# DRV8301_project.net
KiCad netlist of a schematic drawn in Altium Designer
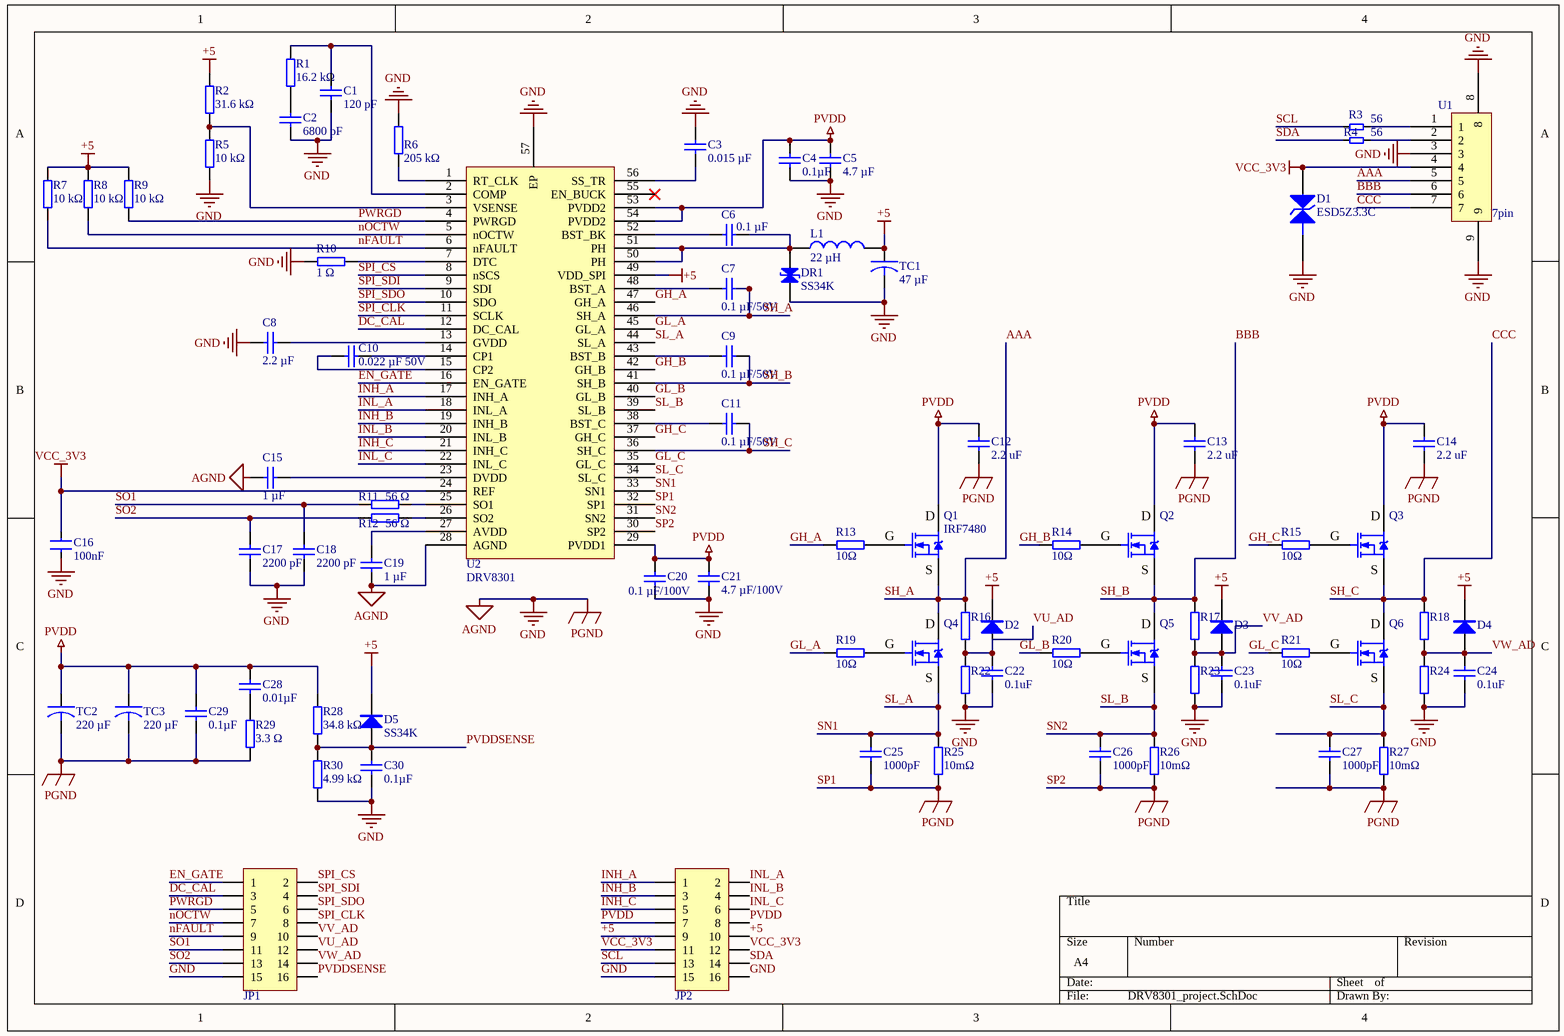
[diagram p0: DRV8301_project.SchDoc]

(export (version "E")
  (design (tool "Eeschema 10.0.6"))
  (components
    (comp (ref "C1") (value "120 pF") (footprint "C 0603_L") (libsource (lib "DRV8301") (part "CAP")))
    (comp (ref "C2") (value "6800 pF") (footprint "C 0603_L") (libsource (lib "DRV8301") (part "CAP")))
    (comp (ref "C3") (value "0.015 µF") (footprint "C 0603_L") (libsource (lib "DRV8301") (part "CAP")))
    (comp (ref "C4") (value "0.1µF") (footprint "C 0603_L") (libsource (lib "DRV8301") (part "CAP")))
    (comp (ref "C5") (value "4.7 µF") (footprint "C 0603_L") (libsource (lib "DRV8301") (part "CAP")))
    (comp (ref "C6") (value "0.1 µF") (footprint "C 0603_L") (libsource (lib "DRV8301") (part "CAP")))
    (comp (ref "C7") (value "0.1 µF/50V") (footprint "C 0603_L") (libsource (lib "DRV8301") (part "CAP")))
    (comp (ref "C8")
      (value "2.2 µF")
      (footprint "C 0603_L")
      (description "2.2 µF  陶瓷电容。大于16V")
      (libsource (lib "DRV8301") (part "CAP"))
    )
    (comp (ref "C9") (value "0.1 µF/50V") (footprint "C 0603_L") (libsource (lib "DRV8301") (part "CAP")))
    (comp (ref "C10")
      (value "0.022 µF 50V")
      (footprint "C 0603_L")
      (description "耐压值要高的陶瓷电容，等于V PIDD1")
      (libsource (lib "DRV8301") (part "CAP"))
    )
    (comp (ref "C11") (value "0.1 µF/50V") (footprint "C 0603_L") (libsource (lib "DRV8301") (part "CAP")))
    (comp (ref "C12") (value "2.2 uF") (footprint "C 0603_L") (libsource (lib "DRV8301") (part "CAP")))
    (comp (ref "C13") (value "2.2 uF") (footprint "C 0603_L") (libsource (lib "DRV8301") (part "CAP")))
    (comp (ref "C14") (value "2.2 uF") (footprint "C 0603_L") (libsource (lib "DRV8301") (part "CAP")))
    (comp (ref "C15") (value "1 µF") (footprint "C 0603_L") (libsource (lib "DRV8301") (part "CAP")))
    (comp (ref "C16")
      (value "100nF")
      (footprint "C 0603_L")
      (description "电容")
      (libsource (lib "DRV8313PWPR") (part "C0603"))
    )
    (comp (ref "C17") (value "2200 pF") (footprint "C 0603_L") (libsource (lib "DRV8301") (part "CAP")))
    (comp (ref "C18") (value "2200 pF") (footprint "C 0603_L") (libsource (lib "DRV8301") (part "CAP")))
    (comp (ref "C19") (value "1 µF") (footprint "C 0603_L") (libsource (lib "DRV8301") (part "CAP")))
    (comp (ref "C20") (value "0.1 µF/100V") (footprint "C 0603_L") (libsource (lib "DRV8301") (part "CAP")))
    (comp (ref "C21") (value "4.7 µF/100V") (footprint "C 0603_L") (libsource (lib "DRV8301") (part "CAP")))
    (comp (ref "C22") (value "0.1uF") (footprint "C 0603_L") (libsource (lib "DRV8301") (part "CAP")))
    (comp (ref "C23") (value "0.1uF") (footprint "C 0603_L") (libsource (lib "DRV8301") (part "CAP")))
    (comp (ref "C24") (value "0.1uF") (footprint "C 0603_L") (libsource (lib "DRV8301") (part "CAP")))
    (comp (ref "C25") (value "1000pF") (footprint "C 0603_L") (libsource (lib "DRV8301") (part "CAP")))
    (comp (ref "C26") (value "1000pF") (footprint "C 0603_L") (libsource (lib "DRV8301") (part "CAP")))
    (comp (ref "C27") (value "1000pF") (footprint "C 0603_L") (libsource (lib "DRV8301") (part "CAP")))
    (comp (ref "C28") (value "0.01µF") (footprint "C 0603_L") (libsource (lib "DRV8301") (part "CAP")))
    (comp (ref "C29") (value "0.1µF") (footprint "C 0603_L") (libsource (lib "DRV8301") (part "CAP")))
    (comp (ref "C30") (value "0.1µF") (footprint "C 0603_L") (libsource (lib "DRV8301") (part "CAP")))
    (comp (ref "D1")
      (value "ESD5Z3.3C")
      (footprint "R 0603_L")
      (description "ESD管")
      (libsource (lib "DRV8313PWPR") (part "ESD"))
    )
    (comp (ref "D2")
      (value "SS34K")
      (footprint "SMA")
      (description "肖特基二极管")
      (fields (field (name "版权归属") "源创客"))
      (libsource (lib "DRV8301") (part "SS34"))
    )
    (comp (ref "D3")
      (value "SS34K")
      (footprint "SMA")
      (description "肖特基二极管")
      (fields (field (name "版权归属") "源创客"))
      (libsource (lib "DRV8301") (part "SS34"))
    )
    (comp (ref "D4")
      (value "SS34K")
      (footprint "SMA")
      (description "肖特基二极管")
      (fields (field (name "版权归属") "源创客"))
      (libsource (lib "DRV8301") (part "SS34"))
    )
    (comp (ref "D5")
      (value "SS34K")
      (footprint "SMA")
      (description "肖特基二极管")
      (fields (field (name "版权归属") "源创客"))
      (libsource (lib "DRV8301") (part "SS34"))
    )
    (comp (ref "DR1")
      (value "SS34K")
      (footprint "SMA")
      (description "瞬态电压抑制二极管")
      (fields (field (name "版权归属") "源创客"))
      (libsource (lib "DRV8301") (part "DR"))
    )
    (comp (ref "JP1")
      (value "Header 8X2")
      (footprint "HDR2X8")
      (description "8*2P接插件")
      (fields (field (name "版权归属") "源创客"))
      (libsource (lib "DRV8301") (part "Header 8X2"))
    )
    (comp (ref "JP2")
      (value "Header 8X2")
      (footprint "HDR2X8")
      (description "8*2P接插件")
      (fields (field (name "版权归属") "源创客"))
      (libsource (lib "DRV8301") (part "Header 8X2"))
    )
    (comp (ref "L1")
      (value "22 µH")
      (footprint "CDRH74")
      (description "电感")
      (fields (field (name "版权归属") "源创客"))
      (libsource (lib "DRV8301") (part "L"))
    )
    (comp (ref "Q1")
      (value "IRF7480")
      (footprint "IRF7480MTRPBF-3pin")
      (description "N沟场效应管")
      (fields (field (name "版权归属") "源创客"))
      (libsource (lib "DRV8301") (part "IRF7480"))
    )
    (comp (ref "Q2")
      (value "IRF7480")
      (footprint "IRF7480MTRPBF-3pin")
      (description "N沟场效应管")
      (fields (field (name "版权归属") "源创客"))
      (libsource (lib "DRV8301") (part "IRF7480"))
    )
    (comp (ref "Q3")
      (value "IRF7480")
      (footprint "IRF7480MTRPBF-3pin")
      (description "N沟场效应管")
      (fields (field (name "版权归属") "源创客"))
      (libsource (lib "DRV8301") (part "IRF7480"))
    )
    (comp (ref "Q4")
      (value "IRF7480")
      (footprint "IRF7480MTRPBF-3pin")
      (description "N沟场效应管")
      (fields (field (name "版权归属") "源创客"))
      (libsource (lib "DRV8301") (part "IRF7480"))
    )
    (comp (ref "Q5")
      (value "IRF7480")
      (footprint "IRF7480MTRPBF-3pin")
      (description "N沟场效应管")
      (fields (field (name "版权归属") "源创客"))
      (libsource (lib "DRV8301") (part "IRF7480"))
    )
    (comp (ref "Q6")
      (value "IRF7480")
      (footprint "IRF7480MTRPBF-3pin")
      (description "N沟场效应管")
      (fields (field (name "版权归属") "源创客"))
      (libsource (lib "DRV8301") (part "IRF7480"))
    )
    (comp (ref "R1") (value "16.2 kΩ") (footprint "R 0603_L") (libsource (lib "DRV8301") (part "RES")))
    (comp (ref "R2") (value "31.6 kΩ") (footprint "R 0603_L") (libsource (lib "DRV8301") (part "RES")))
    (comp (ref "R3")
      (value "56")
      (footprint "R 0603_L")
      (description "电阻")
      (libsource (lib "DRV8313PWPR") (part "R0603"))
    )
    (comp (ref "R4")
      (value "56")
      (footprint "R 0603_L")
      (description "电阻")
      (libsource (lib "DRV8313PWPR") (part "R0603"))
    )
    (comp (ref "R5") (value "10 kΩ") (footprint "R 0603_L") (libsource (lib "DRV8301") (part "RES")))
    (comp (ref "R6") (value "205 kΩ") (footprint "R 0603_L") (libsource (lib "DRV8301") (part "RES")))
    (comp (ref "R7") (value "10 kΩ") (footprint "R 0603_L") (libsource (lib "DRV8301") (part "RES")))
    (comp (ref "R8") (value "10 kΩ") (footprint "R 0603_L") (libsource (lib "DRV8301") (part "RES")))
    (comp (ref "R9") (value "10 kΩ") (footprint "R 0603_L") (libsource (lib "DRV8301") (part "RES")))
    (comp (ref "R10") (value "1 Ω") (footprint "R 0603_L") (libsource (lib "DRV8301") (part "RES")))
    (comp (ref "R11") (value "56 Ω") (footprint "R 0603_L") (libsource (lib "DRV8301") (part "RES")))
    (comp (ref "R12") (value "56 Ω") (footprint "R 0603_L") (libsource (lib "DRV8301") (part "RES")))
    (comp (ref "R13") (value "10Ω") (footprint "R 0603_L") (libsource (lib "DRV8301") (part "RES")))
    (comp (ref "R14") (value "10Ω") (footprint "R 0603_L") (libsource (lib "DRV8301") (part "RES")))
    (comp (ref "R15") (value "10Ω") (footprint "R 0603_L") (libsource (lib "DRV8301") (part "RES")))
    (comp (ref "R16") (value "34.8 kΩ") (footprint "R 0603_L") (libsource (lib "DRV8301") (part "RES")))
    (comp (ref "R17") (value "RES") (footprint "R 0603_L") (libsource (lib "DRV8301") (part "RES")))
    (comp (ref "R18") (value "RES") (footprint "R 0603_L") (libsource (lib "DRV8301") (part "RES")))
    (comp (ref "R19") (value "10Ω") (footprint "R 0603_L") (libsource (lib "DRV8301") (part "RES")))
    (comp (ref "R20") (value "10Ω") (footprint "R 0603_L") (libsource (lib "DRV8301") (part "RES")))
    (comp (ref "R21") (value "10Ω") (footprint "R 0603_L") (libsource (lib "DRV8301") (part "RES")))
    (comp (ref "R22") (value "4.99 kΩ") (footprint "R 0603_L") (libsource (lib "DRV8301") (part "RES")))
    (comp (ref "R23") (value "RES") (footprint "R 0603_L") (libsource (lib "DRV8301") (part "RES")))
    (comp (ref "R24") (value "RES") (footprint "R 0603_L") (libsource (lib "DRV8301") (part "RES")))
    (comp (ref "R25") (value "10mΩ") (footprint "R 0603_L") (libsource (lib "DRV8301") (part "RES")))
    (comp (ref "R26") (value "10mΩ") (footprint "R 0603_L") (libsource (lib "DRV8301") (part "RES")))
    (comp (ref "R27") (value "10mΩ") (footprint "R 0603_L") (libsource (lib "DRV8301") (part "RES")))
    (comp (ref "R28") (value "34.8 kΩ") (footprint "R 0603_L") (libsource (lib "DRV8301") (part "RES")))
    (comp (ref "R29") (value "3.3 Ω") (footprint "R 0603_L") (libsource (lib "DRV8301") (part "RES")))
    (comp (ref "R30") (value "4.99 kΩ") (footprint "R 0603_L") (libsource (lib "DRV8301") (part "RES")))
    (comp (ref "TC1") (value "47 µF") (footprint "C 1210_L") (libsource (lib "DRV8301") (part "CAP-TC")))
    (comp (ref "TC2") (value "220 µF") (footprint "CT 6*6 - V") (libsource (lib "DRV8301") (part "CAP-TC")))
    (comp (ref "TC3") (value "220 µF") (footprint "CT 6*6 - R") (libsource (lib "DRV8301") (part "CAP-TC")))
    (comp (ref "U1")
      (value "7pin")
      (footprint "HC-1.0-7PWT")
      (description "HC-1.0-7PWT")
      (libsource (lib "DRV8313PWPR") (part "connect_7pin"))
    )
    (comp (ref "U2") (value "DRV8301") (footprint "SSOP56") (libsource (lib "DRV8301") (part "DRV8301")))
  )
  (nets
    (net (code "1") (name "+5") (class "Default")
      (node (ref "D2") (pin "2") (pinfunction "K_2") (pintype "passive"))
      (node (ref "D3") (pin "2") (pinfunction "K_2") (pintype "passive"))
      (node (ref "D4") (pin "2") (pinfunction "K_2") (pintype "passive"))
      (node (ref "D5") (pin "2") (pinfunction "K_2") (pintype "passive"))
      (node (ref "JP2") (pin "10") (pinfunction "10_10") (pintype "passive"))
      (node (ref "JP2") (pin "9") (pinfunction "9_9") (pintype "passive"))
      (node (ref "L1") (pin "2") (pinfunction "2_2") (pintype "passive"))
      (node (ref "R2") (pin "2") (pinfunction "2_2") (pintype "passive"))
      (node (ref "R7") (pin "2") (pinfunction "2_2") (pintype "passive"))
      (node (ref "R8") (pin "2") (pinfunction "2_2") (pintype "passive"))
      (node (ref "R9") (pin "2") (pinfunction "2_2") (pintype "passive"))
      (node (ref "TC1") (pin "1") (pinfunction "1_1") (pintype "passive"))
      (node (ref "U2") (pin "49") (pinfunction "VDD_SPI_49") (pintype "passive"))
    )
    (net (code "2") (name "/AAA") (class "Default")
      (node (ref "C7") (pin "1") (pintype "passive"))
      (node (ref "Q1") (pin "2") (pinfunction "S_2") (pintype "passive"))
      (node (ref "Q4") (pin "3") (pinfunction "D_3") (pintype "passive"))
      (node (ref "R16") (pin "2") (pinfunction "2_2") (pintype "passive"))
      (node (ref "U1") (pin "5") (pinfunction "5_5") (pintype "passive"))
      (node (ref "U2") (pin "46") (pinfunction "SH_A_46") (pintype "passive"))
    )
    (net (code "3") (name "/BBB") (class "Default")
      (node (ref "C9") (pin "2") (pintype "passive"))
      (node (ref "Q2") (pin "2") (pinfunction "S_2") (pintype "passive"))
      (node (ref "Q5") (pin "3") (pinfunction "D_3") (pintype "passive"))
      (node (ref "R17") (pin "2") (pinfunction "2_2") (pintype "passive"))
      (node (ref "U1") (pin "6") (pinfunction "6_6") (pintype "passive"))
      (node (ref "U2") (pin "41") (pinfunction "SH_B_41") (pintype "passive"))
    )
    (net (code "4") (name "/CCC") (class "Default")
      (node (ref "C11") (pin "2") (pintype "passive"))
      (node (ref "Q3") (pin "2") (pinfunction "S_2") (pintype "passive"))
      (node (ref "Q6") (pin "3") (pinfunction "D_3") (pintype "passive"))
      (node (ref "R18") (pin "2") (pinfunction "2_2") (pintype "passive"))
      (node (ref "U1") (pin "7") (pinfunction "7_7") (pintype "passive"))
      (node (ref "U2") (pin "36") (pinfunction "SH_C_36") (pintype "passive"))
    )
    (net (code "5") (name "/DC_CAL") (class "Default")
      (node (ref "JP1") (pin "3") (pinfunction "3_3") (pintype "passive"))
      (node (ref "U2") (pin "12") (pinfunction "DC_CAL_12") (pintype "passive"))
    )
    (net (code "6") (name "/EN_GATE") (class "Default")
      (node (ref "JP1") (pin "1") (pinfunction "1_1") (pintype "passive"))
      (node (ref "U2") (pin "16") (pinfunction "EN_GATE_16") (pintype "passive"))
    )
    (net (code "7") (name "/GH_A") (class "Default")
      (node (ref "R13") (pin "1") (pinfunction "1_1") (pintype "passive"))
      (node (ref "U2") (pin "47") (pinfunction "GH_A_47") (pintype "passive"))
    )
    (net (code "8") (name "/GH_B") (class "Default")
      (node (ref "R14") (pin "1") (pinfunction "1_1") (pintype "passive"))
      (node (ref "U2") (pin "42") (pinfunction "GH_B_42") (pintype "passive"))
    )
    (net (code "9") (name "/GH_C") (class "Default")
      (node (ref "R15") (pin "1") (pinfunction "1_1") (pintype "passive"))
      (node (ref "U2") (pin "37") (pinfunction "GH_C_37") (pintype "passive"))
    )
    (net (code "10") (name "/GL_A") (class "Default")
      (node (ref "R19") (pin "1") (pinfunction "1_1") (pintype "passive"))
      (node (ref "U2") (pin "45") (pinfunction "GL_A_45") (pintype "passive"))
    )
    (net (code "11") (name "/GL_B") (class "Default")
      (node (ref "R20") (pin "1") (pinfunction "1_1") (pintype "passive"))
      (node (ref "U2") (pin "40") (pinfunction "GL_B_40") (pintype "passive"))
    )
    (net (code "12") (name "/GL_C") (class "Default")
      (node (ref "R21") (pin "1") (pinfunction "1_1") (pintype "passive"))
      (node (ref "U2") (pin "35") (pinfunction "GL_C_35") (pintype "passive"))
    )
    (net (code "13") (name "/INH_A") (class "Default")
      (node (ref "JP2") (pin "1") (pinfunction "1_1") (pintype "passive"))
      (node (ref "U2") (pin "17") (pinfunction "INH_A_17") (pintype "passive"))
    )
    (net (code "14") (name "/INH_B") (class "Default")
      (node (ref "JP2") (pin "3") (pinfunction "3_3") (pintype "passive"))
      (node (ref "U2") (pin "19") (pinfunction "INH_B_19") (pintype "passive"))
    )
    (net (code "15") (name "/INH_C") (class "Default")
      (node (ref "JP2") (pin "5") (pinfunction "5_5") (pintype "passive"))
      (node (ref "U2") (pin "21") (pinfunction "INH_C_21") (pintype "passive"))
    )
    (net (code "16") (name "/INL_A") (class "Default")
      (node (ref "JP2") (pin "2") (pinfunction "2_2") (pintype "passive"))
      (node (ref "U2") (pin "18") (pinfunction "INL_A_18") (pintype "passive"))
    )
    (net (code "17") (name "/INL_B") (class "Default")
      (node (ref "JP2") (pin "4") (pinfunction "4_4") (pintype "passive"))
      (node (ref "U2") (pin "20") (pinfunction "INL_B_20") (pintype "passive"))
    )
    (net (code "18") (name "/INL_C") (class "Default")
      (node (ref "JP2") (pin "6") (pinfunction "6_6") (pintype "passive"))
      (node (ref "U2") (pin "22") (pinfunction "INL_C_22") (pintype "passive"))
    )
    (net (code "19") (name "/PVDDSENSE") (class "Default")
      (node (ref "C30") (pin "1") (pintype "passive"))
      (node (ref "D5") (pin "1") (pinfunction "A_1") (pintype "passive"))
      (node (ref "JP1") (pin "16") (pinfunction "16_16") (pintype "passive"))
      (node (ref "R28") (pin "1") (pinfunction "1_1") (pintype "passive"))
      (node (ref "R30") (pin "2") (pinfunction "2_2") (pintype "passive"))
    )
    (net (code "20") (name "/PWRGD") (class "Default")
      (node (ref "JP1") (pin "5") (pinfunction "5_5") (pintype "passive"))
      (node (ref "R9") (pin "1") (pinfunction "1_1") (pintype "passive"))
      (node (ref "U2") (pin "4") (pinfunction "PWRGD_4") (pintype "passive"))
    )
    (net (code "21") (name "/SCL") (class "Default")
      (node (ref "JP2") (pin "13") (pinfunction "13_13") (pintype "passive"))
      (node (ref "R3") (pin "1") (pinfunction "1_1") (pintype "passive"))
    )
    (net (code "22") (name "/SDA") (class "Default")
      (node (ref "JP2") (pin "14") (pinfunction "14_14") (pintype "passive"))
      (node (ref "R4") (pin "1") (pinfunction "1_1") (pintype "passive"))
    )
    (net (code "23") (name "/SL_A") (class "Default")
      (node (ref "C25") (pin "1") (pintype "passive"))
      (node (ref "Q4") (pin "2") (pinfunction "S_2") (pintype "passive"))
      (node (ref "R25") (pin "2") (pinfunction "2_2") (pintype "passive"))
      (node (ref "U2") (pin "33") (pinfunction "SN1_33") (pintype "passive"))
      (node (ref "U2") (pin "44") (pinfunction "SL_A_44") (pintype "passive"))
    )
    (net (code "24") (name "/SL_B") (class "Default")
      (node (ref "C26") (pin "1") (pintype "passive"))
      (node (ref "Q5") (pin "2") (pinfunction "S_2") (pintype "passive"))
      (node (ref "R26") (pin "2") (pinfunction "2_2") (pintype "passive"))
      (node (ref "U2") (pin "31") (pinfunction "SN2_31") (pintype "passive"))
      (node (ref "U2") (pin "39") (pinfunction "SL_B_39") (pintype "passive"))
    )
    (net (code "25") (name "/SL_C") (class "Default")
      (node (ref "C27") (pin "1") (pintype "passive"))
      (node (ref "Q6") (pin "2") (pinfunction "S_2") (pintype "passive"))
      (node (ref "R27") (pin "2") (pinfunction "2_2") (pintype "passive"))
      (node (ref "U2") (pin "34") (pinfunction "SL_C_34") (pintype "passive"))
    )
    (net (code "26") (name "/SO1") (class "Default")
      (node (ref "C18") (pin "1") (pintype "passive"))
      (node (ref "JP1") (pin "11") (pinfunction "11_11") (pintype "passive"))
      (node (ref "R11") (pin "1") (pinfunction "1_1") (pintype "passive"))
    )
    (net (code "27") (name "/SO2") (class "Default")
      (node (ref "C17") (pin "1") (pintype "passive"))
      (node (ref "JP1") (pin "13") (pinfunction "13_13") (pintype "passive"))
      (node (ref "R12") (pin "1") (pinfunction "1_1") (pintype "passive"))
    )
    (net (code "28") (name "/SPI_CLK") (class "Default")
      (node (ref "JP1") (pin "8") (pinfunction "8_8") (pintype "passive"))
      (node (ref "U2") (pin "11") (pinfunction "SCLK_11") (pintype "passive"))
    )
    (net (code "29") (name "/SPI_CS") (class "Default")
      (node (ref "JP1") (pin "2") (pinfunction "2_2") (pintype "passive"))
      (node (ref "U2") (pin "8") (pinfunction "nSCS_8") (pintype "passive"))
    )
    (net (code "30") (name "/SPI_SDI") (class "Default")
      (node (ref "JP1") (pin "4") (pinfunction "4_4") (pintype "passive"))
      (node (ref "U2") (pin "9") (pinfunction "SDI_9") (pintype "passive"))
    )
    (net (code "31") (name "/SPI_SDO") (class "Default")
      (node (ref "JP1") (pin "6") (pinfunction "6_6") (pintype "passive"))
      (node (ref "U2") (pin "10") (pinfunction "SDO_10") (pintype "passive"))
    )
    (net (code "32") (name "/VU_AD") (class "Default")
      (node (ref "C22") (pin "1") (pintype "passive"))
      (node (ref "D2") (pin "1") (pinfunction "A_1") (pintype "passive"))
      (node (ref "JP1") (pin "12") (pinfunction "12_12") (pintype "passive"))
      (node (ref "R16") (pin "1") (pinfunction "1_1") (pintype "passive"))
      (node (ref "R22") (pin "2") (pinfunction "2_2") (pintype "passive"))
    )
    (net (code "33") (name "/VV_AD") (class "Default")
      (node (ref "C23") (pin "1") (pintype "passive"))
      (node (ref "D3") (pin "1") (pinfunction "A_1") (pintype "passive"))
      (node (ref "JP1") (pin "10") (pinfunction "10_10") (pintype "passive"))
      (node (ref "R17") (pin "1") (pinfunction "1_1") (pintype "passive"))
      (node (ref "R23") (pin "2") (pinfunction "2_2") (pintype "passive"))
    )
    (net (code "34") (name "/VW_AD") (class "Default")
      (node (ref "C24") (pin "1") (pintype "passive"))
      (node (ref "D4") (pin "1") (pinfunction "A_1") (pintype "passive"))
      (node (ref "JP1") (pin "14") (pinfunction "14_14") (pintype "passive"))
      (node (ref "R18") (pin "1") (pinfunction "1_1") (pintype "passive"))
      (node (ref "R24") (pin "2") (pinfunction "2_2") (pintype "passive"))
    )
    (net (code "35") (name "/nFAULT") (class "Default")
      (node (ref "JP1") (pin "9") (pinfunction "9_9") (pintype "passive"))
      (node (ref "R7") (pin "1") (pinfunction "1_1") (pintype "passive"))
      (node (ref "U2") (pin "6") (pinfunction "nFAULT_6") (pintype "passive"))
    )
    (net (code "36") (name "/nOCTW") (class "Default")
      (node (ref "JP1") (pin "7") (pinfunction "7_7") (pintype "passive"))
      (node (ref "R8") (pin "1") (pinfunction "1_1") (pintype "passive"))
      (node (ref "U2") (pin "5") (pinfunction "nOCTW_5") (pintype "passive"))
    )
    (net (code "37") (name "AGND") (class "Default")
      (node (ref "C1") (pin "2") (pintype "passive"))
      (node (ref "C12") (pin "2") (pintype "passive"))
      (node (ref "C13") (pin "2") (pintype "passive"))
      (node (ref "C14") (pin "2") (pintype "passive"))
      (node (ref "C15") (pin "1") (pintype "passive"))
      (node (ref "C16") (pin "2") (pinfunction "2_2") (pintype "passive"))
      (node (ref "C17") (pin "2") (pintype "passive"))
      (node (ref "C18") (pin "2") (pintype "passive"))
      (node (ref "C19") (pin "1") (pintype "passive"))
      (node (ref "C2") (pin "2") (pintype "passive"))
      (node (ref "C20") (pin "2") (pintype "passive"))
      (node (ref "C21") (pin "2") (pintype "passive"))
      (node (ref "C22") (pin "2") (pintype "passive"))
      (node (ref "C23") (pin "2") (pintype "passive"))
      (node (ref "C24") (pin "2") (pintype "passive"))
      (node (ref "C25") (pin "2") (pintype "passive"))
      (node (ref "C26") (pin "2") (pintype "passive"))
      (node (ref "C27") (pin "2") (pintype "passive"))
      (node (ref "C29") (pin "2") (pintype "passive"))
      (node (ref "C3") (pin "2") (pintype "passive"))
      (node (ref "C30") (pin "2") (pintype "passive"))
      (node (ref "C4") (pin "2") (pintype "passive"))
      (node (ref "C5") (pin "2") (pintype "passive"))
      (node (ref "C8") (pin "2") (pintype "passive"))
      (node (ref "D1") (pin "1") (pinfunction "A_1") (pintype "passive"))
      (node (ref "DR1") (pin "2") (pinfunction "K_2") (pintype "passive"))
      (node (ref "JP1") (pin "15") (pinfunction "15_15") (pintype "passive"))
      (node (ref "JP2") (pin "15") (pinfunction "15_15") (pintype "passive"))
      (node (ref "JP2") (pin "16") (pinfunction "16_16") (pintype "passive"))
      (node (ref "R10") (pin "1") (pinfunction "1_1") (pintype "passive"))
      (node (ref "R22") (pin "1") (pinfunction "1_1") (pintype "passive"))
      (node (ref "R23") (pin "1") (pinfunction "1_1") (pintype "passive"))
      (node (ref "R24") (pin "1") (pinfunction "1_1") (pintype "passive"))
      (node (ref "R25") (pin "1") (pinfunction "1_1") (pintype "passive"))
      (node (ref "R26") (pin "1") (pinfunction "1_1") (pintype "passive"))
      (node (ref "R27") (pin "1") (pinfunction "1_1") (pintype "passive"))
      (node (ref "R29") (pin "1") (pinfunction "1_1") (pintype "passive"))
      (node (ref "R30") (pin "1") (pinfunction "1_1") (pintype "passive"))
      (node (ref "R5") (pin "1") (pinfunction "1_1") (pintype "passive"))
      (node (ref "R6") (pin "2") (pinfunction "2_2") (pintype "passive"))
      (node (ref "TC1") (pin "2") (pinfunction "2_2") (pintype "passive"))
      (node (ref "TC2") (pin "2") (pinfunction "2_2") (pintype "passive"))
      (node (ref "TC3") (pin "2") (pinfunction "2_2") (pintype "passive"))
      (node (ref "U1") (pin "3") (pinfunction "3_3") (pintype "passive"))
      (node (ref "U1") (pin "8") (pinfunction "8_8") (pintype "passive"))
      (node (ref "U1") (pin "9") (pinfunction "9_9") (pintype "passive"))
      (node (ref "U2") (pin "28") (pinfunction "AGND_28") (pintype "passive"))
      (node (ref "U2") (pin "30") (pinfunction "SP2_30") (pintype "passive"))
      (node (ref "U2") (pin "32") (pinfunction "SP1_32") (pintype "passive"))
      (node (ref "U2") (pin "57") (pinfunction "EP_57") (pintype "passive"))
    )
    (net (code "38") (name "Net-(C2-Pad1)") (class "Default")
      (node (ref "C2") (pin "1") (pintype "passive"))
      (node (ref "R1") (pin "1") (pinfunction "1_1") (pintype "passive"))
    )
    (net (code "39") (name "Net-(C28-Pad2)") (class "Default")
      (node (ref "C28") (pin "2") (pintype "passive"))
      (node (ref "R29") (pin "2") (pinfunction "2_2") (pintype "passive"))
    )
    (net (code "40") (name "Net-(DR1-A)") (class "Default")
      (node (ref "C6") (pin "2") (pintype "passive"))
      (node (ref "DR1") (pin "1") (pinfunction "A_1") (pintype "passive"))
      (node (ref "L1") (pin "1") (pinfunction "1_1") (pintype "passive"))
      (node (ref "U2") (pin "50") (pinfunction "PH_50") (pintype "passive"))
      (node (ref "U2") (pin "51") (pinfunction "PH_51") (pintype "passive"))
    )
    (net (code "41") (name "Net-(Q1-G)") (class "Default")
      (node (ref "Q1") (pin "1") (pinfunction "G_1") (pintype "passive"))
      (node (ref "R13") (pin "2") (pinfunction "2_2") (pintype "passive"))
    )
    (net (code "42") (name "Net-(Q2-G)") (class "Default")
      (node (ref "Q2") (pin "1") (pinfunction "G_1") (pintype "passive"))
      (node (ref "R14") (pin "2") (pinfunction "2_2") (pintype "passive"))
    )
    (net (code "43") (name "Net-(Q3-G)") (class "Default")
      (node (ref "Q3") (pin "1") (pinfunction "G_1") (pintype "passive"))
      (node (ref "R15") (pin "2") (pinfunction "2_2") (pintype "passive"))
    )
    (net (code "44") (name "Net-(Q4-G)") (class "Default")
      (node (ref "Q4") (pin "1") (pinfunction "G_1") (pintype "passive"))
      (node (ref "R19") (pin "2") (pinfunction "2_2") (pintype "passive"))
    )
    (net (code "45") (name "Net-(Q5-G)") (class "Default")
      (node (ref "Q5") (pin "1") (pinfunction "G_1") (pintype "passive"))
      (node (ref "R20") (pin "2") (pinfunction "2_2") (pintype "passive"))
    )
    (net (code "46") (name "Net-(Q6-G)") (class "Default")
      (node (ref "Q6") (pin "1") (pinfunction "G_1") (pintype "passive"))
      (node (ref "R21") (pin "2") (pinfunction "2_2") (pintype "passive"))
    )
    (net (code "47") (name "Net-(R3-Pad2)") (class "Default")
      (node (ref "R3") (pin "2") (pinfunction "2_2") (pintype "passive"))
      (node (ref "U1") (pin "1") (pinfunction "1_1") (pintype "passive"))
    )
    (net (code "48") (name "Net-(R4-Pad2)") (class "Default")
      (node (ref "R4") (pin "2") (pinfunction "2_2") (pintype "passive"))
      (node (ref "U1") (pin "2") (pinfunction "2_2") (pintype "passive"))
    )
    (net (code "49") (name "Net-(U2-AVDD)") (class "Default")
      (node (ref "C19") (pin "2") (pintype "passive"))
      (node (ref "U2") (pin "27") (pinfunction "AVDD_27") (pintype "passive"))
    )
    (net (code "50") (name "Net-(U2-BST_A)") (class "Default")
      (node (ref "C7") (pin "2") (pintype "passive"))
      (node (ref "U2") (pin "48") (pinfunction "BST_A_48") (pintype "passive"))
    )
    (net (code "51") (name "Net-(U2-BST_B)") (class "Default")
      (node (ref "C9") (pin "1") (pintype "passive"))
      (node (ref "U2") (pin "43") (pinfunction "BST_B_43") (pintype "passive"))
    )
    (net (code "52") (name "Net-(U2-BST_BK)") (class "Default")
      (node (ref "C6") (pin "1") (pintype "passive"))
      (node (ref "U2") (pin "52") (pinfunction "BST_BK_52") (pintype "passive"))
    )
    (net (code "53") (name "Net-(U2-BST_C)") (class "Default")
      (node (ref "C11") (pin "1") (pintype "passive"))
      (node (ref "U2") (pin "38") (pinfunction "BST_C_38") (pintype "passive"))
    )
    (net (code "54") (name "Net-(U2-COMP)") (class "Default")
      (node (ref "C1") (pin "1") (pintype "passive"))
      (node (ref "R1") (pin "2") (pinfunction "2_2") (pintype "passive"))
      (node (ref "U2") (pin "2") (pinfunction "COMP_2") (pintype "passive"))
    )
    (net (code "55") (name "Net-(U2-CP1)") (class "Default")
      (node (ref "C10") (pin "2") (pintype "passive"))
      (node (ref "U2") (pin "14") (pinfunction "CP1_14") (pintype "passive"))
    )
    (net (code "56") (name "Net-(U2-CP2)") (class "Default")
      (node (ref "C10") (pin "1") (pintype "passive"))
      (node (ref "U2") (pin "15") (pinfunction "CP2_15") (pintype "passive"))
    )
    (net (code "57") (name "Net-(U2-DTC)") (class "Default")
      (node (ref "R10") (pin "2") (pinfunction "2_2") (pintype "passive"))
      (node (ref "U2") (pin "7") (pinfunction "DTC_7") (pintype "passive"))
    )
    (net (code "58") (name "Net-(U2-DVDD)") (class "Default")
      (node (ref "C15") (pin "2") (pintype "passive"))
      (node (ref "U2") (pin "23") (pinfunction "DVDD_23") (pintype "passive"))
    )
    (net (code "59") (name "Net-(U2-GVDD)") (class "Default")
      (node (ref "C8") (pin "1") (pintype "passive"))
      (node (ref "U2") (pin "13") (pinfunction "GVDD_13") (pintype "passive"))
    )
    (net (code "60") (name "Net-(U2-RT_CLK)") (class "Default")
      (node (ref "R6") (pin "1") (pinfunction "1_1") (pintype "passive"))
      (node (ref "U2") (pin "1") (pinfunction "RT_CLK_1") (pintype "passive"))
    )
    (net (code "61") (name "Net-(U2-SO1)") (class "Default")
      (node (ref "R11") (pin "2") (pinfunction "2_2") (pintype "passive"))
      (node (ref "U2") (pin "25") (pinfunction "SO1_25") (pintype "passive"))
    )
    (net (code "62") (name "Net-(U2-SO2)") (class "Default")
      (node (ref "R12") (pin "2") (pinfunction "2_2") (pintype "passive"))
      (node (ref "U2") (pin "26") (pinfunction "SO2_26") (pintype "passive"))
    )
    (net (code "63") (name "Net-(U2-SS_TR)") (class "Default")
      (node (ref "C3") (pin "1") (pintype "passive"))
      (node (ref "U2") (pin "56") (pinfunction "SS_TR_56") (pintype "passive"))
    )
    (net (code "64") (name "Net-(U2-VSENSE)") (class "Default")
      (node (ref "R2") (pin "1") (pinfunction "1_1") (pintype "passive"))
      (node (ref "R5") (pin "2") (pinfunction "2_2") (pintype "passive"))
      (node (ref "U2") (pin "3") (pinfunction "VSENSE_3") (pintype "passive"))
    )
    (net (code "65") (name "PVDD") (class "Default")
      (node (ref "C12") (pin "1") (pintype "passive"))
      (node (ref "C13") (pin "1") (pintype "passive"))
      (node (ref "C14") (pin "1") (pintype "passive"))
      (node (ref "C20") (pin "1") (pintype "passive"))
      (node (ref "C21") (pin "1") (pintype "passive"))
      (node (ref "C28") (pin "1") (pintype "passive"))
      (node (ref "C29") (pin "1") (pintype "passive"))
      (node (ref "C4") (pin "1") (pintype "passive"))
      (node (ref "C5") (pin "1") (pintype "passive"))
      (node (ref "JP2") (pin "7") (pinfunction "7_7") (pintype "passive"))
      (node (ref "JP2") (pin "8") (pinfunction "8_8") (pintype "passive"))
      (node (ref "Q1") (pin "3") (pinfunction "D_3") (pintype "passive"))
      (node (ref "Q2") (pin "3") (pinfunction "D_3") (pintype "passive"))
      (node (ref "Q3") (pin "3") (pinfunction "D_3") (pintype "passive"))
      (node (ref "R28") (pin "2") (pinfunction "2_2") (pintype "passive"))
      (node (ref "TC2") (pin "1") (pinfunction "1_1") (pintype "passive"))
      (node (ref "TC3") (pin "1") (pinfunction "1_1") (pintype "passive"))
      (node (ref "U2") (pin "29") (pinfunction "PVDD1_29") (pintype "passive"))
      (node (ref "U2") (pin "53") (pinfunction "PVDD2_53") (pintype "passive"))
      (node (ref "U2") (pin "54") (pinfunction "PVDD2_54") (pintype "passive"))
    )
    (net (code "66") (name "VCC_3V3") (class "Default")
      (node (ref "C16") (pin "1") (pinfunction "1_1") (pintype "passive"))
      (node (ref "D1") (pin "2") (pinfunction "K_2") (pintype "passive"))
      (node (ref "JP2") (pin "11") (pinfunction "11_11") (pintype "passive"))
      (node (ref "JP2") (pin "12") (pinfunction "12_12") (pintype "passive"))
      (node (ref "U1") (pin "4") (pinfunction "4_4") (pintype "passive"))
      (node (ref "U2") (pin "24") (pinfunction "REF_24") (pintype "passive"))
    )
    (net (code "67") (name "unconnected-(U2-EN_BUCK-Pad55)") (class "Default")
      (node (ref "U2") (pin "55") (pinfunction "EN_BUCK_55") (pintype "passive+no_connect"))
    )
  )
)
